# Solarladeregler.net
KiCad netlist of a schematic drawn in EAGLE
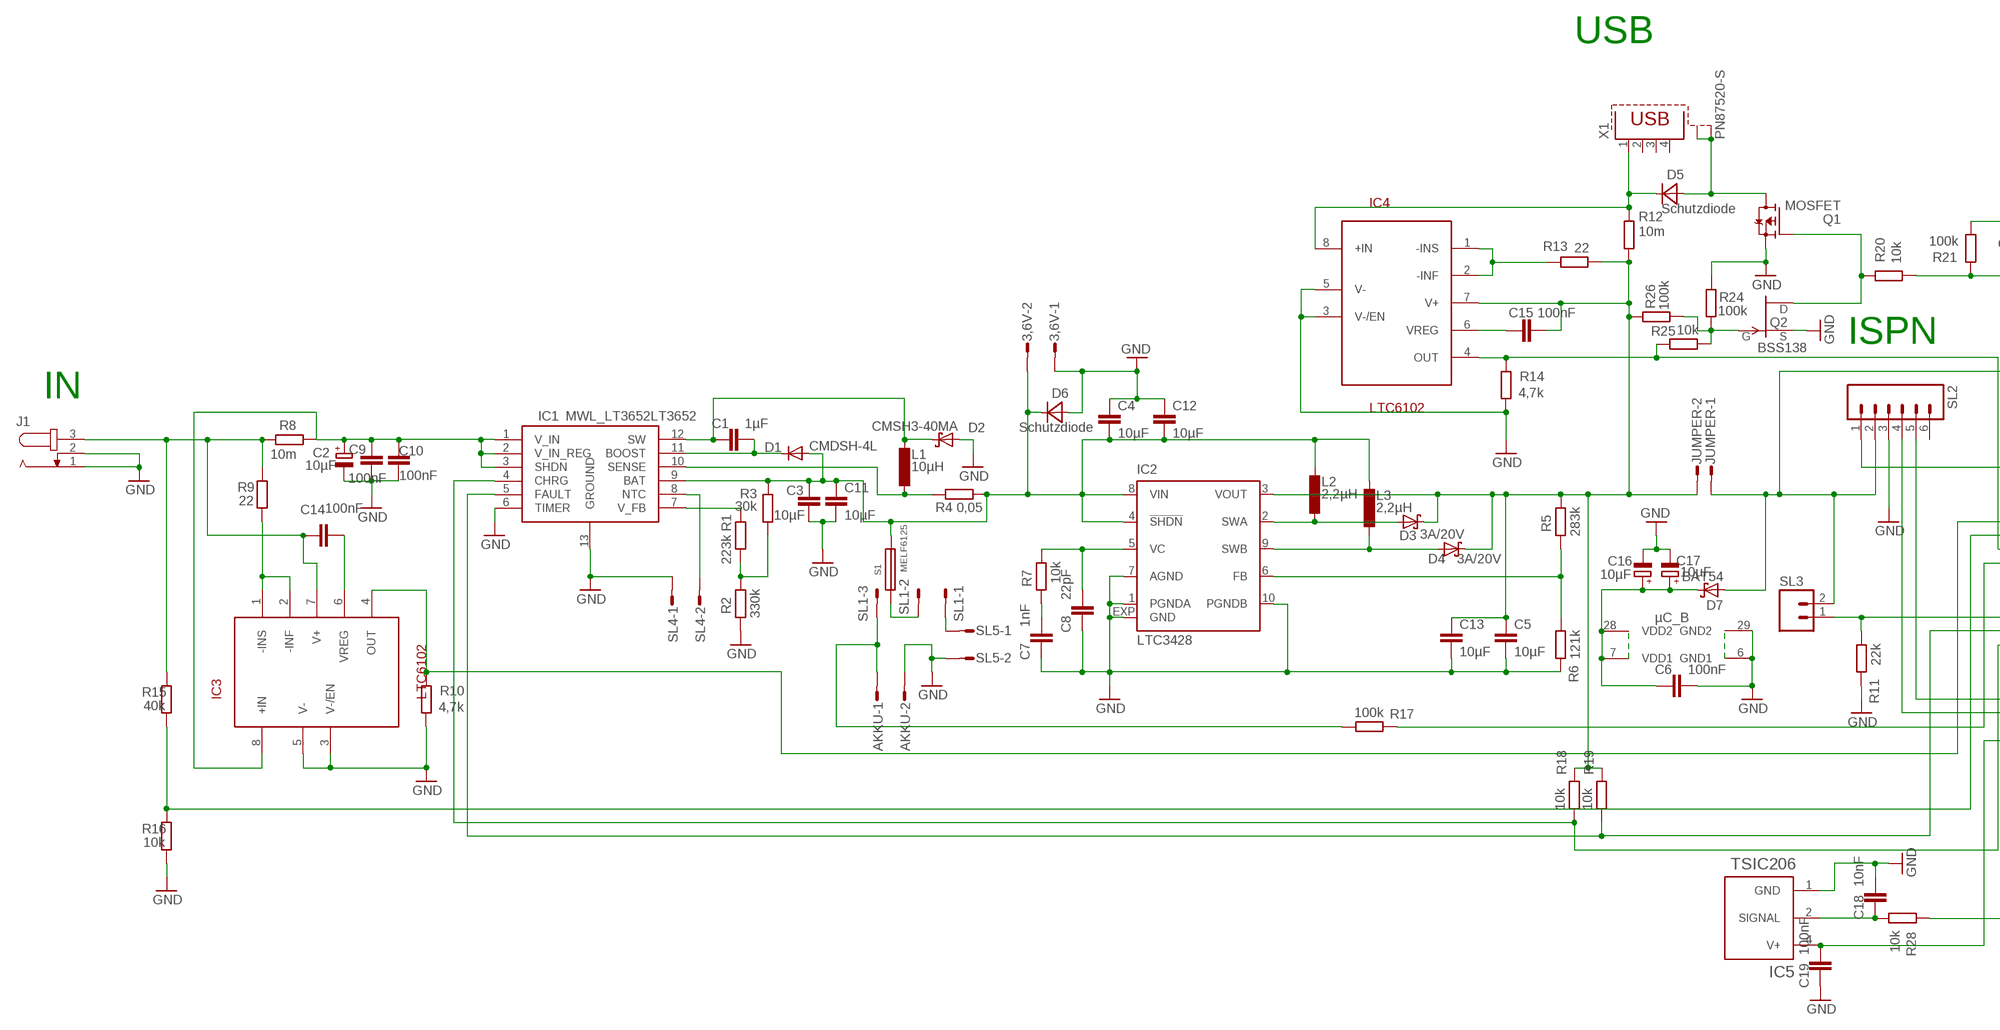
[diagram p0: schematic, sheet 1, part 1 of 2]
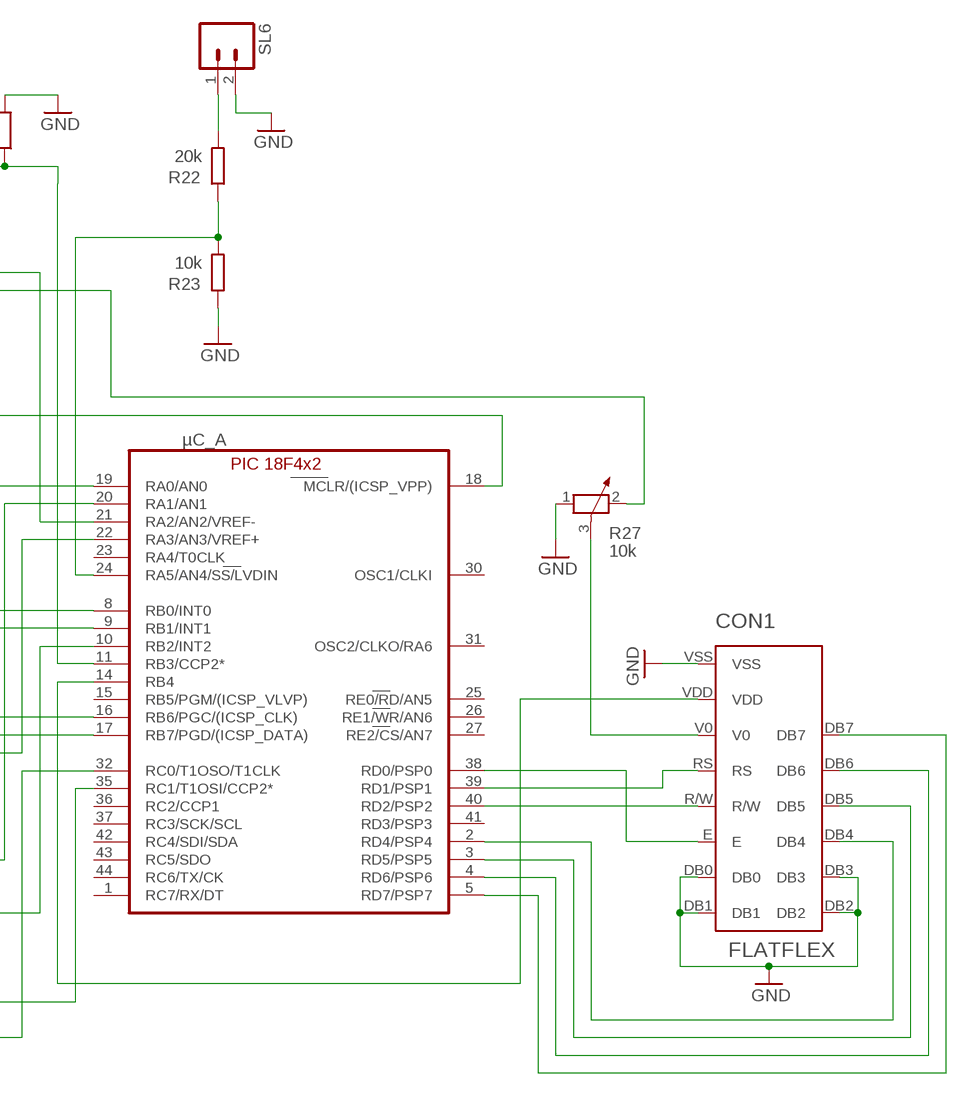
[diagram p1: schematic, sheet 1, part 2 of 2]

(export (version "E")
  (design (tool "Eeschema 10.0.6"))
  (components
    (comp (ref "3,6V")
      (value "M02S")
      (footprint "eagle-import:02P")
      (libsource (lib "eagle-import") (part "M02S"))
    )
    (comp (ref "AKKU")
      (value "M02S")
      (footprint "eagle-import:02P")
      (libsource (lib "eagle-import") (part "M02S"))
    )
    (comp (ref "C1")
      (value "1µF")
      (footprint "eagle-import:C0805")
      (libsource (lib "eagle-import") (part "C-EUC0805"))
    )
    (comp (ref "C2")
      (value "10µF")
      (footprint "eagle-import:153CLV-0505")
      (libsource (lib "eagle-import") (part "CPOL-EU153CLV-0505"))
    )
    (comp (ref "C3")
      (value "10µF")
      (footprint "eagle-import:C0805")
      (libsource (lib "eagle-import") (part "C-EUC0805"))
    )
    (comp (ref "C4")
      (value "10µF")
      (footprint "eagle-import:C0805")
      (libsource (lib "eagle-import") (part "C-EUC0805"))
    )
    (comp (ref "C5")
      (value "10µF")
      (footprint "eagle-import:C0805")
      (libsource (lib "eagle-import") (part "C-EUC0805"))
    )
    (comp (ref "C6")
      (value "100nF")
      (footprint "eagle-import:C0805")
      (libsource (lib "eagle-import") (part "C-EUC0805"))
    )
    (comp (ref "C7")
      (value "1nF")
      (footprint "eagle-import:C0805")
      (libsource (lib "eagle-import") (part "C-EUC0805"))
    )
    (comp (ref "C8")
      (value "22pF")
      (footprint "eagle-import:C0805")
      (libsource (lib "eagle-import") (part "C-EUC0805"))
    )
    (comp (ref "C9")
      (value "100nF")
      (footprint "eagle-import:C0805")
      (libsource (lib "eagle-import") (part "C-EUC0805"))
    )
    (comp (ref "C10")
      (value "100nF")
      (footprint "eagle-import:C0805")
      (libsource (lib "eagle-import") (part "C-EUC0805"))
    )
    (comp (ref "C11")
      (value "10µF")
      (footprint "eagle-import:C0805")
      (libsource (lib "eagle-import") (part "C-EUC0805"))
    )
    (comp (ref "C12")
      (value "10µF")
      (footprint "eagle-import:C0805")
      (libsource (lib "eagle-import") (part "C-EUC0805"))
    )
    (comp (ref "C13")
      (value "10µF")
      (footprint "eagle-import:C0805")
      (libsource (lib "eagle-import") (part "C-EUC0805"))
    )
    (comp (ref "C14")
      (value "100nF")
      (footprint "eagle-import:C0805")
      (libsource (lib "eagle-import") (part "C-EUC0805"))
    )
    (comp (ref "C15")
      (value "100nF")
      (footprint "eagle-import:C0805")
      (libsource (lib "eagle-import") (part "C-EUC0805"))
    )
    (comp (ref "C16")
      (value "10µF")
      (footprint "eagle-import:153CLV-0505")
      (libsource (lib "eagle-import") (part "CPOL-EU153CLV-0505"))
    )
    (comp (ref "C17")
      (value "10µF")
      (footprint "eagle-import:153CLV-0505")
      (libsource (lib "eagle-import") (part "CPOL-EU153CLV-0505"))
    )
    (comp (ref "C18")
      (value "10nF")
      (footprint "eagle-import:C0805")
      (libsource (lib "eagle-import") (part "C-EUC0805"))
    )
    (comp (ref "C19")
      (value "100nF")
      (footprint "eagle-import:C0805")
      (libsource (lib "eagle-import") (part "C-EUC0805"))
    )
    (comp (ref "CON1")
      (value "FLATFLEX")
      (footprint "eagle-import:FLATFLEX")
      (libsource (lib "eagle-import") (part "FLATFLEX"))
    )
    (comp (ref "D1")
      (value "CMDSH-4L")
      (footprint "eagle-import:SOD123")
      (libsource (lib "eagle-import") (part "MBR0520LT"))
    )
    (comp (ref "D2")
      (value "CMSH3-40MA")
      (footprint "eagle-import:SMB")
      (libsource (lib "eagle-import") (part "SCHOTTKY-DIODESMD"))
    )
    (comp (ref "D3")
      (value "3A/20V")
      (footprint "eagle-import:SMC")
      (libsource (lib "eagle-import") (part "MBRS30T32"))
    )
    (comp (ref "D4")
      (value "3A/20V")
      (footprint "eagle-import:SMC")
      (libsource (lib "eagle-import") (part "MBRS30T32"))
    )
    (comp (ref "D5")
      (value "Schutzdiode")
      (footprint "eagle-import:SMA")
      (libsource (lib "eagle-import") (part "MBRA340T3"))
    )
    (comp (ref "D6")
      (value "Schutzdiode")
      (footprint "eagle-import:SMA")
      (libsource (lib "eagle-import") (part "MBRA340T3"))
    )
    (comp (ref "D7")
      (value "BAT54")
      (footprint "eagle-import:SOT23")
      (libsource (lib "eagle-import") (part "BAT54"))
    )
    (comp (ref "IC1")
      (value "MWL_LT3652LT3652")
      (footprint "eagle-import:DFN12DD3X3")
      (libsource (lib "eagle-import") (part "MWL_LT3652LT3652"))
    )
    (comp (ref "IC2")
      (value "LTC3428")
      (footprint "eagle-import:DFN10-3X3")
      (libsource (lib "eagle-import") (part "LTC3428"))
    )
    (comp (ref "IC3")
      (value "LTC6102")
      (footprint "eagle-import:MSOP8")
      (libsource (lib "eagle-import") (part "LTC6102"))
    )
    (comp (ref "IC4")
      (value "LTC6102")
      (footprint "eagle-import:MSOP8")
      (libsource (lib "eagle-import") (part "LTC6102"))
    )
    (comp (ref "IC5")
      (value "TSIC206")
      (footprint "eagle-import:SO08")
      (libsource (lib "eagle-import") (part "TSIC206"))
    )
    (comp (ref "J1")
      (value "JACK-PLUG0")
      (footprint "eagle-import:SPC4077")
      (libsource (lib "eagle-import") (part "JACK-PLUG0"))
    )
    (comp (ref "JUMPER")
      (value "M02S")
      (footprint "eagle-import:02P")
      (libsource (lib "eagle-import") (part "M02S"))
    )
    (comp (ref "L1")
      (value "10µH")
      (footprint "eagle-import:POWER-CHOKE_WE-TPC")
      (libsource (lib "eagle-import") (part "L-EUWE-TPC"))
    )
    (comp (ref "L2")
      (value "2,2µH")
      (footprint "eagle-import:POWER-CHOKE_WE-TPC")
      (libsource (lib "eagle-import") (part "L-EUWE-TPC"))
    )
    (comp (ref "L3")
      (value "2,2µH")
      (footprint "eagle-import:POWER-CHOKE_WE-TPC")
      (libsource (lib "eagle-import") (part "L-EUWE-TPC"))
    )
    (comp (ref "Q1")
      (value "MOSFET")
      (footprint "eagle-import:TO252")
      (libsource (lib "eagle-import") (part "FDD4141TO252"))
    )
    (comp (ref "Q2")
      (value "BSS138")
      (footprint "eagle-import:SOT23")
      (libsource (lib "eagle-import") (part "?548SST4"))
    )
    (comp (ref "R1")
      (value "223k")
      (footprint "eagle-import:R0805")
      (libsource (lib "eagle-import") (part "R-EU_R0805"))
    )
    (comp (ref "R2")
      (value "330k")
      (footprint "eagle-import:R0805")
      (libsource (lib "eagle-import") (part "R-EU_R0805"))
    )
    (comp (ref "R3")
      (value "30k")
      (footprint "eagle-import:R0805")
      (libsource (lib "eagle-import") (part "R-EU_R0805"))
    )
    (comp (ref "R4")
      (value "0,05")
      (footprint "eagle-import:R0805")
      (libsource (lib "eagle-import") (part "R-EU_R0805"))
    )
    (comp (ref "R5")
      (value "283k")
      (footprint "eagle-import:R0805")
      (libsource (lib "eagle-import") (part "R-EU_R0805"))
    )
    (comp (ref "R6")
      (value "121k")
      (footprint "eagle-import:R0805")
      (libsource (lib "eagle-import") (part "R-EU_R0805"))
    )
    (comp (ref "R7")
      (value "10k")
      (footprint "eagle-import:R0805")
      (libsource (lib "eagle-import") (part "R-EU_R0805"))
    )
    (comp (ref "R8")
      (value "10m")
      (footprint "eagle-import:R2512")
      (libsource (lib "eagle-import") (part "R-EU_R2512"))
    )
    (comp (ref "R9")
      (value "22")
      (footprint "eagle-import:R0805")
      (libsource (lib "eagle-import") (part "R-EU_R0805"))
    )
    (comp (ref "R10")
      (value "4,7k")
      (footprint "eagle-import:R0805")
      (libsource (lib "eagle-import") (part "R-EU_R0805"))
    )
    (comp (ref "R11")
      (value "22k")
      (footprint "eagle-import:R0805")
      (libsource (lib "eagle-import") (part "R-EU_R0805"))
    )
    (comp (ref "R12")
      (value "10m")
      (footprint "eagle-import:R2512")
      (libsource (lib "eagle-import") (part "R-EU_R2512"))
    )
    (comp (ref "R13")
      (value "22")
      (footprint "eagle-import:R0805")
      (libsource (lib "eagle-import") (part "R-EU_R0805"))
    )
    (comp (ref "R14")
      (value "4,7k")
      (footprint "eagle-import:R0805")
      (libsource (lib "eagle-import") (part "R-EU_R0805"))
    )
    (comp (ref "R15")
      (value "40k")
      (footprint "eagle-import:R0805")
      (libsource (lib "eagle-import") (part "R-EU_R0805"))
    )
    (comp (ref "R16")
      (value "10k")
      (footprint "eagle-import:R0805")
      (libsource (lib "eagle-import") (part "R-EU_R0805"))
    )
    (comp (ref "R17")
      (value "100k")
      (footprint "eagle-import:R0805")
      (libsource (lib "eagle-import") (part "R-EU_R0805"))
    )
    (comp (ref "R18")
      (value "10k")
      (footprint "eagle-import:R0805")
      (libsource (lib "eagle-import") (part "R-EU_R0805"))
    )
    (comp (ref "R19")
      (value "10k")
      (footprint "eagle-import:R0805")
      (libsource (lib "eagle-import") (part "R-EU_R0805"))
    )
    (comp (ref "R20")
      (value "10k")
      (footprint "eagle-import:R0805")
      (libsource (lib "eagle-import") (part "R-EU_R0805"))
    )
    (comp (ref "R21")
      (value "100k")
      (footprint "eagle-import:R0805")
      (libsource (lib "eagle-import") (part "R-EU_R0805"))
    )
    (comp (ref "R22")
      (value "20k")
      (footprint "eagle-import:R0805")
      (libsource (lib "eagle-import") (part "R-EU_R0805"))
    )
    (comp (ref "R23")
      (value "10k")
      (footprint "eagle-import:R0805")
      (libsource (lib "eagle-import") (part "R-EU_R0805"))
    )
    (comp (ref "R24")
      (value "100k")
      (footprint "eagle-import:R0805")
      (libsource (lib "eagle-import") (part "R-EU_R0805"))
    )
    (comp (ref "R25")
      (value "10k")
      (footprint "eagle-import:R0805")
      (libsource (lib "eagle-import") (part "R-EU_R0805"))
    )
    (comp (ref "R26")
      (value "100k")
      (footprint "eagle-import:R0805")
      (libsource (lib "eagle-import") (part "R-EU_R0805"))
    )
    (comp (ref "R27")
      (value "10k")
      (footprint "eagle-import:PT-10")
      (libsource (lib "eagle-import") (part "POTENTIOMETER_PT-10"))
    )
    (comp (ref "R28")
      (value "10k")
      (footprint "eagle-import:R0805")
      (libsource (lib "eagle-import") (part "R-EU_R0805"))
    )
    (comp (ref "S1")
      (value "MELF6125")
      (footprint "eagle-import:MELF6125")
      (libsource (lib "eagle-import") (part "MELF6125"))
    )
    (comp (ref "SL1")
      (value "M03S")
      (footprint "eagle-import:03P")
      (libsource (lib "eagle-import") (part "M03S"))
    )
    (comp (ref "SL2")
      (value "M06")
      (footprint "eagle-import:06P")
      (libsource (lib "eagle-import") (part "M06"))
    )
    (comp (ref "SL3")
      (value "M02")
      (footprint "eagle-import:02P")
      (libsource (lib "eagle-import") (part "M02"))
    )
    (comp (ref "SL4")
      (value "M02S")
      (footprint "eagle-import:02P")
      (libsource (lib "eagle-import") (part "M02S"))
    )
    (comp (ref "SL5")
      (value "M02S")
      (footprint "eagle-import:02P")
      (libsource (lib "eagle-import") (part "M02S"))
    )
    (comp (ref "SL6")
      (value "M02")
      (footprint "eagle-import:02P")
      (libsource (lib "eagle-import") (part "M02"))
    )
    (comp (ref "X1")
      (value "PN87520-S")
      (footprint "eagle-import:PN87520-S")
      (libsource (lib "eagle-import") (part "PN87520-S"))
    )
    (comp (ref "µC")
      (value "PIC18F4X2TQFP44")
      (footprint "eagle-import:TQFP44")
      (libsource (lib "eagle-import") (part "PIC18F4X2TQFP44"))
    )
  )
  (nets
    (net (code "1") (name "/OSC1{slash}CLKI") (class "Default")
      (node (ref "µC") (pin "30") (pinfunction "OSC1/CLKI_30") (pintype "power_in"))
    )
    (net (code "2") (name "/OSC2{slash}CLKO{slash}RA6") (class "Default")
      (node (ref "µC") (pin "31") (pinfunction "OSC2/CLKO/RA6_31") (pintype "power_in"))
    )
    (net (code "3") (name "GND") (class "Default")
      (node (ref "3,6V") (pin "1") (pinfunction "S_1") (pintype "passive"))
      (node (ref "AKKU") (pin "2") (pinfunction "S_2") (pintype "passive"))
      (node (ref "C10") (pin "2") (pinfunction "2_2") (pintype "passive"))
      (node (ref "C11") (pin "2") (pinfunction "2_2") (pintype "passive"))
      (node (ref "C12") (pin "1") (pinfunction "1_1") (pintype "passive"))
      (node (ref "C13") (pin "2") (pinfunction "2_2") (pintype "passive"))
      (node (ref "C16") (pin "-") (pinfunction "-_-") (pintype "passive"))
      (node (ref "C17") (pin "-") (pinfunction "-_-") (pintype "passive"))
      (node (ref "C18") (pin "1") (pinfunction "1_1") (pintype "passive"))
      (node (ref "C19") (pin "2") (pinfunction "2_2") (pintype "passive"))
      (node (ref "C2") (pin "-") (pinfunction "-_-") (pintype "passive"))
      (node (ref "C3") (pin "2") (pinfunction "2_2") (pintype "passive"))
      (node (ref "C4") (pin "1") (pinfunction "1_1") (pintype "passive"))
      (node (ref "C5") (pin "2") (pinfunction "2_2") (pintype "passive"))
      (node (ref "C6") (pin "1") (pinfunction "1_1") (pintype "passive"))
      (node (ref "C7") (pin "2") (pinfunction "2_2") (pintype "passive"))
      (node (ref "C8") (pin "2") (pinfunction "2_2") (pintype "passive"))
      (node (ref "C9") (pin "2") (pinfunction "2_2") (pintype "passive"))
      (node (ref "CON1") (pin "DB0") (pinfunction "DB0_DB0") (pintype "bidirectional"))
      (node (ref "CON1") (pin "DB1") (pinfunction "DB1_DB1") (pintype "bidirectional"))
      (node (ref "CON1") (pin "DB2") (pinfunction "DB2_DB2") (pintype "bidirectional"))
      (node (ref "CON1") (pin "DB3") (pinfunction "DB3_DB3") (pintype "bidirectional"))
      (node (ref "CON1") (pin "VSS") (pinfunction "VSS_VSS") (pintype "bidirectional"))
      (node (ref "D2") (pin "A") (pinfunction "A_A") (pintype "passive"))
      (node (ref "D6") (pin "A") (pinfunction "A_A") (pintype "passive"))
      (node (ref "IC1") (pin "13") (pinfunction "GROUND_13") (pintype "bidirectional"))
      (node (ref "IC1") (pin "6") (pinfunction "TIMER_6") (pintype "bidirectional"))
      (node (ref "IC2") (pin "1") (pinfunction "PGNDA_1") (pintype "passive"))
      (node (ref "IC2") (pin "10") (pinfunction "PGNDB_10") (pintype "passive"))
      (node (ref "IC2") (pin "7") (pinfunction "AGND_7") (pintype "passive"))
      (node (ref "IC2") (pin "EXP") (pinfunction "GND_EXP") (pintype "power_in"))
      (node (ref "IC3") (pin "3") (pinfunction "V-/EN_3") (pintype "bidirectional"))
      (node (ref "IC3") (pin "5") (pinfunction "V-_5") (pintype "bidirectional"))
      (node (ref "IC4") (pin "3") (pinfunction "V-/EN_3") (pintype "bidirectional"))
      (node (ref "IC4") (pin "5") (pinfunction "V-_5") (pintype "bidirectional"))
      (node (ref "IC5") (pin "1") (pinfunction "GND_1") (pintype "bidirectional"))
      (node (ref "J1") (pin "1") (pinfunction "1_1") (pintype "passive"))
      (node (ref "J1") (pin "2") (pinfunction "2_2") (pintype "passive"))
      (node (ref "Q1") (pin "2") (pinfunction "S_2") (pintype "passive"))
      (node (ref "Q2") (pin "2") (pinfunction "S_2") (pintype "passive"))
      (node (ref "R10") (pin "2") (pinfunction "2_2") (pintype "passive"))
      (node (ref "R11") (pin "2") (pinfunction "2_2") (pintype "passive"))
      (node (ref "R14") (pin "2") (pinfunction "2_2") (pintype "passive"))
      (node (ref "R16") (pin "2") (pinfunction "2_2") (pintype "passive"))
      (node (ref "R2") (pin "2") (pinfunction "2_2") (pintype "passive"))
      (node (ref "R21") (pin "2") (pinfunction "2_2") (pintype "passive"))
      (node (ref "R23") (pin "1") (pinfunction "1_1") (pintype "passive"))
      (node (ref "R24") (pin "1") (pinfunction "1_1") (pintype "passive"))
      (node (ref "R27") (pin "1") (pinfunction "1_1") (pintype "passive"))
      (node (ref "R6") (pin "2") (pinfunction "2_2") (pintype "passive"))
      (node (ref "SL2") (pin "3") (pinfunction "3_3") (pintype "passive"))
      (node (ref "SL4") (pin "1") (pinfunction "S_1") (pintype "passive"))
      (node (ref "SL5") (pin "2") (pinfunction "S_2") (pintype "passive"))
      (node (ref "SL6") (pin "2") (pinfunction "2_2") (pintype "passive"))
      (node (ref "µC") (pin "29") (pinfunction "GND2_29") (pintype "power_in"))
      (node (ref "µC") (pin "6") (pinfunction "GND1_6") (pintype "power_in"))
    )
    (net (code "4") (name "Net-(3,6VB-S)") (class "Default")
      (node (ref "3,6V") (pin "2") (pinfunction "S_2") (pintype "passive"))
      (node (ref "C11") (pin "1") (pinfunction "1_1") (pintype "passive"))
      (node (ref "C12") (pin "2") (pinfunction "2_2") (pintype "passive"))
      (node (ref "C3") (pin "1") (pinfunction "1_1") (pintype "passive"))
      (node (ref "C4") (pin "2") (pinfunction "2_2") (pintype "passive"))
      (node (ref "D1") (pin "A") (pinfunction "A_A") (pintype "passive"))
      (node (ref "D6") (pin "C") (pinfunction "C_C") (pintype "passive"))
      (node (ref "IC1") (pin "9") (pinfunction "BAT_9") (pintype "output"))
      (node (ref "IC2") (pin "4") (pinfunction "~{SHDN}_4") (pintype "open_collector"))
      (node (ref "IC2") (pin "8") (pinfunction "VIN_8") (pintype "power_in"))
      (node (ref "L2") (pin "2") (pinfunction "2_2") (pintype "passive"))
      (node (ref "L3") (pin "2") (pinfunction "2_2") (pintype "passive"))
      (node (ref "R3") (pin "2") (pinfunction "2_2") (pintype "passive"))
      (node (ref "R4") (pin "1") (pinfunction "1_1") (pintype "passive"))
      (node (ref "S1") (pin "P$4") (pinfunction "P$2_P$4") (pintype "bidirectional"))
    )
    (net (code "5") (name "Net-(AKKUA-S)") (class "Default")
      (node (ref "AKKU") (pin "1") (pinfunction "S_1") (pintype "passive"))
      (node (ref "R17") (pin "1") (pinfunction "1_1") (pintype "passive"))
      (node (ref "SL1") (pin "3") (pinfunction "S_3") (pintype "passive"))
    )
    (net (code "6") (name "Net-(C7-Pad1)") (class "Default")
      (node (ref "C7") (pin "1") (pinfunction "1_1") (pintype "passive"))
      (node (ref "R7") (pin "2") (pinfunction "2_2") (pintype "passive"))
    )
    (net (code "7") (name "Net-(CON1-PadV0)") (class "Default")
      (node (ref "CON1") (pin "V0") (pinfunction "V0_V0") (pintype "bidirectional"))
      (node (ref "R27") (pin "3") (pinfunction "3_3") (pintype "passive"))
    )
    (net (code "8") (name "Net-(D7-A)") (class "Default")
      (node (ref "D7") (pin "1") (pinfunction "A_1") (pintype "passive"))
      (node (ref "JUMPER") (pin "1") (pinfunction "S_1") (pintype "passive"))
      (node (ref "R27") (pin "2") (pinfunction "2_2") (pintype "passive"))
      (node (ref "SL2") (pin "2") (pinfunction "2_2") (pintype "passive"))
      (node (ref "SL3") (pin "2") (pinfunction "2_2") (pintype "passive"))
    )
    (net (code "9") (name "Net-(D7-C)") (class "Default")
      (node (ref "C16") (pin "+") (pinfunction "+_+") (pintype "passive"))
      (node (ref "C17") (pin "+") (pinfunction "+_+") (pintype "passive"))
      (node (ref "C6") (pin "2") (pinfunction "2_2") (pintype "passive"))
      (node (ref "D7") (pin "3") (pinfunction "C_3") (pintype "passive"))
      (node (ref "µC") (pin "28") (pinfunction "VDD2_28") (pintype "power_in"))
      (node (ref "µC") (pin "7") (pinfunction "VDD1_7") (pintype "power_in"))
    )
    (net (code "10") (name "Net-(IC1-BOOST)") (class "Default")
      (node (ref "C1") (pin "1") (pinfunction "1_1") (pintype "passive"))
      (node (ref "D1") (pin "C") (pinfunction "C_C") (pintype "passive"))
      (node (ref "IC1") (pin "11") (pinfunction "BOOST_11") (pintype "bidirectional"))
    )
    (net (code "11") (name "Net-(IC1-CHRG)") (class "Default")
      (node (ref "IC1") (pin "4") (pinfunction "CHRG_4") (pintype "output"))
      (node (ref "R18") (pin "1") (pinfunction "1_1") (pintype "passive"))
      (node (ref "µC") (pin "10") (pinfunction "RB2/INT2_10") (pintype "bidirectional"))
    )
    (net (code "12") (name "Net-(IC1-FAULT)") (class "Default")
      (node (ref "IC1") (pin "5") (pinfunction "FAULT_5") (pintype "output"))
      (node (ref "R19") (pin "1") (pinfunction "1_1") (pintype "passive"))
      (node (ref "µC") (pin "9") (pinfunction "RB1/INT1_9") (pintype "bidirectional"))
    )
    (net (code "13") (name "Net-(IC1-NTC)") (class "Default")
      (node (ref "IC1") (pin "8") (pinfunction "NTC_8") (pintype "input"))
      (node (ref "SL4") (pin "2") (pinfunction "S_2") (pintype "passive"))
    )
    (net (code "14") (name "Net-(IC1-SENSE)") (class "Default")
      (node (ref "IC1") (pin "10") (pinfunction "SENSE_10") (pintype "bidirectional"))
      (node (ref "L1") (pin "1") (pinfunction "1_1") (pintype "passive"))
      (node (ref "R4") (pin "2") (pinfunction "2_2") (pintype "passive"))
    )
    (net (code "15") (name "Net-(IC1-SHDN)") (class "Default")
      (node (ref "C10") (pin "1") (pinfunction "1_1") (pintype "passive"))
      (node (ref "C2") (pin "+") (pinfunction "+_+") (pintype "passive"))
      (node (ref "C9") (pin "1") (pinfunction "1_1") (pintype "passive"))
      (node (ref "IC1") (pin "1") (pinfunction "V_IN_1") (pintype "input"))
      (node (ref "IC1") (pin "2") (pinfunction "V_IN_REG_2") (pintype "input"))
      (node (ref "IC1") (pin "3") (pinfunction "SHDN_3") (pintype "input"))
      (node (ref "IC3") (pin "8") (pinfunction "+IN_8") (pintype "bidirectional"))
      (node (ref "R8") (pin "1") (pinfunction "1_1") (pintype "passive"))
    )
    (net (code "16") (name "Net-(IC1-SW)") (class "Default")
      (node (ref "C1") (pin "2") (pinfunction "2_2") (pintype "passive"))
      (node (ref "D2") (pin "C") (pinfunction "C_C") (pintype "passive"))
      (node (ref "IC1") (pin "12") (pinfunction "SW_12") (pintype "output"))
      (node (ref "L1") (pin "2") (pinfunction "2_2") (pintype "passive"))
    )
    (net (code "17") (name "Net-(IC1-V_FB)") (class "Default")
      (node (ref "IC1") (pin "7") (pinfunction "V_FB_7") (pintype "bidirectional"))
      (node (ref "R1") (pin "1") (pinfunction "1_1") (pintype "passive"))
    )
    (net (code "18") (name "Net-(IC2-FB)") (class "Default")
      (node (ref "IC2") (pin "6") (pinfunction "FB_6") (pintype "input"))
      (node (ref "R5") (pin "2") (pinfunction "2_2") (pintype "passive"))
      (node (ref "R6") (pin "1") (pinfunction "1_1") (pintype "passive"))
    )
    (net (code "19") (name "Net-(IC2-SWA)") (class "Default")
      (node (ref "D3") (pin "A") (pinfunction "A_A") (pintype "passive"))
      (node (ref "IC2") (pin "2") (pinfunction "SWA_2") (pintype "open_collector"))
      (node (ref "L2") (pin "1") (pinfunction "1_1") (pintype "passive"))
    )
    (net (code "20") (name "Net-(IC2-SWB)") (class "Default")
      (node (ref "D4") (pin "A") (pinfunction "A_A") (pintype "passive"))
      (node (ref "IC2") (pin "9") (pinfunction "SWB_9") (pintype "passive"))
      (node (ref "L3") (pin "1") (pinfunction "1_1") (pintype "passive"))
    )
    (net (code "21") (name "Net-(IC2-VC)") (class "Default")
      (node (ref "C8") (pin "1") (pinfunction "1_1") (pintype "passive"))
      (node (ref "IC2") (pin "5") (pinfunction "VC_5") (pintype "input"))
      (node (ref "R7") (pin "1") (pinfunction "1_1") (pintype "passive"))
    )
    (net (code "22") (name "Net-(IC2-VOUT)") (class "Default")
      (node (ref "C13") (pin "1") (pinfunction "1_1") (pintype "passive"))
      (node (ref "C15") (pin "2") (pinfunction "2_2") (pintype "passive"))
      (node (ref "C5") (pin "1") (pinfunction "1_1") (pintype "passive"))
      (node (ref "D3") (pin "C") (pinfunction "C_C") (pintype "passive"))
      (node (ref "D4") (pin "C") (pinfunction "C_C") (pintype "passive"))
      (node (ref "IC2") (pin "3") (pinfunction "VOUT_3") (pintype "input"))
      (node (ref "IC4") (pin "7") (pinfunction "V+_7") (pintype "bidirectional"))
      (node (ref "JUMPER") (pin "2") (pinfunction "S_2") (pintype "passive"))
      (node (ref "R12") (pin "2") (pinfunction "2_2") (pintype "passive"))
      (node (ref "R13") (pin "2") (pinfunction "2_2") (pintype "passive"))
      (node (ref "R18") (pin "2") (pinfunction "2_2") (pintype "passive"))
      (node (ref "R19") (pin "2") (pinfunction "2_2") (pintype "passive"))
      (node (ref "R26") (pin "1") (pinfunction "1_1") (pintype "passive"))
      (node (ref "R5") (pin "1") (pinfunction "1_1") (pintype "passive"))
    )
    (net (code "23") (name "Net-(IC3--INF)") (class "Default")
      (node (ref "IC3") (pin "1") (pinfunction "-INS_1") (pintype "bidirectional"))
      (node (ref "IC3") (pin "2") (pinfunction "-INF_2") (pintype "bidirectional"))
      (node (ref "R9") (pin "2") (pinfunction "2_2") (pintype "passive"))
    )
    (net (code "24") (name "Net-(IC3-OUT)") (class "Default")
      (node (ref "IC3") (pin "4") (pinfunction "OUT_4") (pintype "bidirectional"))
      (node (ref "R10") (pin "1") (pinfunction "1_1") (pintype "passive"))
      (node (ref "µC") (pin "19") (pinfunction "RA0/AN0_19") (pintype "bidirectional"))
    )
    (net (code "25") (name "Net-(IC3-V+)") (class "Default")
      (node (ref "C14") (pin "1") (pinfunction "1_1") (pintype "passive"))
      (node (ref "IC3") (pin "7") (pinfunction "V+_7") (pintype "bidirectional"))
      (node (ref "J1") (pin "3") (pinfunction "3_3") (pintype "passive"))
      (node (ref "R15") (pin "1") (pinfunction "1_1") (pintype "passive"))
      (node (ref "R8") (pin "2") (pinfunction "2_2") (pintype "passive"))
      (node (ref "R9") (pin "1") (pinfunction "1_1") (pintype "passive"))
    )
    (net (code "26") (name "Net-(IC3-VREG)") (class "Default")
      (node (ref "C14") (pin "2") (pinfunction "2_2") (pintype "passive"))
      (node (ref "IC3") (pin "6") (pinfunction "VREG_6") (pintype "bidirectional"))
    )
    (net (code "27") (name "Net-(IC4-+IN)") (class "Default")
      (node (ref "D5") (pin "C") (pinfunction "C_C") (pintype "passive"))
      (node (ref "IC4") (pin "8") (pinfunction "+IN_8") (pintype "bidirectional"))
      (node (ref "R12") (pin "1") (pinfunction "1_1") (pintype "passive"))
      (node (ref "X1") (pin "1") (pinfunction "1_1") (pintype "passive"))
    )
    (net (code "28") (name "Net-(IC4--INF)") (class "Default")
      (node (ref "IC4") (pin "1") (pinfunction "-INS_1") (pintype "bidirectional"))
      (node (ref "IC4") (pin "2") (pinfunction "-INF_2") (pintype "bidirectional"))
      (node (ref "R13") (pin "1") (pinfunction "1_1") (pintype "passive"))
    )
    (net (code "29") (name "Net-(IC4-OUT)") (class "Default")
      (node (ref "IC4") (pin "4") (pinfunction "OUT_4") (pintype "bidirectional"))
      (node (ref "R14") (pin "1") (pinfunction "1_1") (pintype "passive"))
      (node (ref "R25") (pin "1") (pinfunction "1_1") (pintype "passive"))
      (node (ref "µC") (pin "21") (pinfunction "RA2/AN2/VREF-_21") (pintype "bidirectional"))
    )
    (net (code "30") (name "Net-(IC4-VREG)") (class "Default")
      (node (ref "C15") (pin "1") (pinfunction "1_1") (pintype "passive"))
      (node (ref "IC4") (pin "6") (pinfunction "VREG_6") (pintype "bidirectional"))
    )
    (net (code "31") (name "Net-(IC5-SIGNAL)") (class "Default")
      (node (ref "C18") (pin "2") (pinfunction "2_2") (pintype "passive"))
      (node (ref "IC5") (pin "2") (pinfunction "SIGNAL_2") (pintype "bidirectional"))
      (node (ref "R28") (pin "2") (pinfunction "2_2") (pintype "passive"))
    )
    (net (code "32") (name "Net-(IC5-V+)") (class "Default")
      (node (ref "C19") (pin "1") (pinfunction "1_1") (pintype "passive"))
      (node (ref "IC5") (pin "4") (pinfunction "V+_4") (pintype "bidirectional"))
      (node (ref "µC") (pin "32") (pinfunction "RC0/T1OSO/T1CLK_32") (pintype "bidirectional"))
    )
    (net (code "33") (name "Net-(Q1-D)") (class "Default")
      (node (ref "D5") (pin "A") (pinfunction "A_A") (pintype "passive"))
      (node (ref "Q1") (pin "3") (pinfunction "D_3") (pintype "passive"))
      (node (ref "X1") (pin "S1") (pinfunction "S1_S1") (pintype "passive"))
      (node (ref "X1") (pin "S2") (pinfunction "S2_S2") (pintype "passive"))
    )
    (net (code "34") (name "Net-(Q1-G)") (class "Default")
      (node (ref "Q1") (pin "1") (pinfunction "G_1") (pintype "passive"))
      (node (ref "Q2") (pin "1") (pinfunction "D_1") (pintype "passive"))
      (node (ref "R20") (pin "1") (pinfunction "1_1") (pintype "passive"))
    )
    (net (code "35") (name "Net-(Q2-G)") (class "Default")
      (node (ref "Q2") (pin "3") (pinfunction "G_3") (pintype "passive"))
      (node (ref "R24") (pin "2") (pinfunction "2_2") (pintype "passive"))
      (node (ref "R25") (pin "2") (pinfunction "2_2") (pintype "passive"))
      (node (ref "R26") (pin "2") (pinfunction "2_2") (pintype "passive"))
    )
    (net (code "36") (name "Net-(R1-Pad2)") (class "Default")
      (node (ref "R1") (pin "2") (pinfunction "2_2") (pintype "passive"))
      (node (ref "R2") (pin "1") (pinfunction "1_1") (pintype "passive"))
      (node (ref "R3") (pin "1") (pinfunction "1_1") (pintype "passive"))
    )
    (net (code "37") (name "Net-(R22-Pad2)") (class "Default")
      (node (ref "R22") (pin "2") (pinfunction "2_2") (pintype "passive"))
      (node (ref "SL6") (pin "1") (pinfunction "1_1") (pintype "passive"))
    )
    (net (code "38") (name "Net-(S1-P$1)") (class "Default")
      (node (ref "S1") (pin "P$3") (pinfunction "P$1_P$3") (pintype "bidirectional"))
      (node (ref "SL1") (pin "2") (pinfunction "S_2") (pintype "passive"))
    )
    (net (code "39") (name "Net-(SL1A-S)") (class "Default")
      (node (ref "SL1") (pin "1") (pinfunction "S_1") (pintype "passive"))
      (node (ref "SL5") (pin "1") (pinfunction "S_1") (pintype "passive"))
    )
    (net (code "40") (name "Net-(µCA-MCLR{slash}(ICSP_VPP))") (class "Default")
      (node (ref "SL2") (pin "1") (pinfunction "1_1") (pintype "passive"))
      (node (ref "µC") (pin "18") (pinfunction "MCLR/(ICSP_VPP)_18") (pintype "power_in"))
    )
    (net (code "41") (name "Net-(µCA-RA1{slash}AN1)") (class "Default")
      (node (ref "R15") (pin "2") (pinfunction "2_2") (pintype "passive"))
      (node (ref "R16") (pin "1") (pinfunction "1_1") (pintype "passive"))
      (node (ref "µC") (pin "20") (pinfunction "RA1/AN1_20") (pintype "bidirectional"))
    )
    (net (code "42") (name "Net-(µCA-RA3{slash}AN3{slash}VREF+)") (class "Default")
      (node (ref "R17") (pin "2") (pinfunction "2_2") (pintype "passive"))
      (node (ref "µC") (pin "22") (pinfunction "RA3/AN3/VREF+_22") (pintype "bidirectional"))
    )
    (net (code "43") (name "Net-(µCA-RA5{slash}AN4{slash}SS{slash}LVDIN)") (class "Default")
      (node (ref "R22") (pin "1") (pinfunction "1_1") (pintype "passive"))
      (node (ref "R23") (pin "2") (pinfunction "2_2") (pintype "passive"))
      (node (ref "µC") (pin "24") (pinfunction "RA5/AN4/SS/LVDIN_24") (pintype "bidirectional"))
    )
    (net (code "44") (name "Net-(µCA-RB0{slash}INT0)") (class "Default")
      (node (ref "R11") (pin "1") (pinfunction "1_1") (pintype "passive"))
      (node (ref "SL3") (pin "1") (pinfunction "1_1") (pintype "passive"))
      (node (ref "µC") (pin "8") (pinfunction "RB0/INT0_8") (pintype "bidirectional"))
    )
    (net (code "45") (name "Net-(µCA-RB3{slash}CCP2*)") (class "Default")
      (node (ref "R20") (pin "2") (pinfunction "2_2") (pintype "passive"))
      (node (ref "R21") (pin "1") (pinfunction "1_1") (pintype "passive"))
      (node (ref "µC") (pin "11") (pinfunction "RB3/CCP2*_11") (pintype "bidirectional"))
    )
    (net (code "46") (name "Net-(µCA-RB4)") (class "Default")
      (node (ref "CON1") (pin "VDD") (pinfunction "VDD_VDD") (pintype "bidirectional"))
      (node (ref "µC") (pin "14") (pinfunction "RB4_14") (pintype "bidirectional"))
    )
    (net (code "47") (name "Net-(µCA-RB6{slash}PGC{slash}(ICSP_CLK))") (class "Default")
      (node (ref "SL2") (pin "5") (pinfunction "5_5") (pintype "passive"))
      (node (ref "µC") (pin "16") (pinfunction "RB6/PGC/(ICSP_CLK)_16") (pintype "bidirectional"))
    )
    (net (code "48") (name "Net-(µCA-RB7{slash}PGD{slash}(ICSP_DATA))") (class "Default")
      (node (ref "SL2") (pin "4") (pinfunction "4_4") (pintype "passive"))
      (node (ref "µC") (pin "17") (pinfunction "RB7/PGD/(ICSP_DATA)_17") (pintype "bidirectional"))
    )
    (net (code "49") (name "Net-(µCA-RC1{slash}T1OSI{slash}CCP2*)") (class "Default")
      (node (ref "R28") (pin "1") (pinfunction "1_1") (pintype "passive"))
      (node (ref "µC") (pin "35") (pinfunction "RC1/T1OSI/CCP2*_35") (pintype "bidirectional"))
    )
    (net (code "50") (name "Net-(µCA-RD0{slash}PSP0)") (class "Default")
      (node (ref "CON1") (pin "E") (pinfunction "E_E") (pintype "bidirectional"))
      (node (ref "µC") (pin "38") (pinfunction "RD0/PSP0_38") (pintype "bidirectional"))
    )
    (net (code "51") (name "Net-(µCA-RD1{slash}PSP1)") (class "Default")
      (node (ref "CON1") (pin "RS") (pinfunction "RS_RS") (pintype "bidirectional"))
      (node (ref "µC") (pin "39") (pinfunction "RD1/PSP1_39") (pintype "bidirectional"))
    )
    (net (code "52") (name "Net-(µCA-RD2{slash}PSP2)") (class "Default")
      (node (ref "CON1") (pin "R/W") (pinfunction "R/W_R/W") (pintype "bidirectional"))
      (node (ref "µC") (pin "40") (pinfunction "RD2/PSP2_40") (pintype "bidirectional"))
    )
    (net (code "53") (name "Net-(µCA-RD4{slash}PSP4)") (class "Default")
      (node (ref "CON1") (pin "DB4") (pinfunction "DB4_DB4") (pintype "bidirectional"))
      (node (ref "µC") (pin "2") (pinfunction "RD4/PSP4_2") (pintype "bidirectional"))
    )
    (net (code "54") (name "Net-(µCA-RD5{slash}PSP5)") (class "Default")
      (node (ref "CON1") (pin "DB5") (pinfunction "DB5_DB5") (pintype "bidirectional"))
      (node (ref "µC") (pin "3") (pinfunction "RD5/PSP5_3") (pintype "bidirectional"))
    )
    (net (code "55") (name "Net-(µCA-RD6{slash}PSP6)") (class "Default")
      (node (ref "CON1") (pin "DB6") (pinfunction "DB6_DB6") (pintype "bidirectional"))
      (node (ref "µC") (pin "4") (pinfunction "RD6/PSP6_4") (pintype "bidirectional"))
    )
    (net (code "56") (name "Net-(µCA-RD7{slash}PSP7)") (class "Default")
      (node (ref "CON1") (pin "DB7") (pinfunction "DB7_DB7") (pintype "bidirectional"))
      (node (ref "µC") (pin "5") (pinfunction "RD7/PSP7_5") (pintype "bidirectional"))
    )
    (net (code "57") (name "unconnected-(SL2-Pad6)") (class "Default")
      (node (ref "SL2") (pin "6") (pinfunction "6_6") (pintype "passive"))
    )
    (net (code "58") (name "unconnected-(X1-Pad2)") (class "Default")
      (node (ref "X1") (pin "2") (pinfunction "2_2") (pintype "passive"))
    )
    (net (code "59") (name "unconnected-(X1-Pad3)") (class "Default")
      (node (ref "X1") (pin "3") (pinfunction "3_3") (pintype "passive"))
    )
    (net (code "60") (name "unconnected-(X1-Pad4)") (class "Default")
      (node (ref "X1") (pin "4") (pinfunction "4_4") (pintype "passive"))
    )
    (net (code "61") (name "unconnected-(µCA-RA4{slash}T0CLK-Pad23)") (class "Default")
      (node (ref "µC") (pin "23") (pinfunction "RA4/T0CLK_23") (pintype "bidirectional"))
    )
    (net (code "62") (name "unconnected-(µCA-RB5{slash}PGM{slash}(ICSP_VLVP)-Pad15)") (class "Default")
      (node (ref "µC") (pin "15") (pinfunction "RB5/PGM/(ICSP_VLVP)_15") (pintype "bidirectional"))
    )
    (net (code "63") (name "unconnected-(µCA-RC2{slash}CCP1-Pad36)") (class "Default")
      (node (ref "µC") (pin "36") (pinfunction "RC2/CCP1_36") (pintype "bidirectional"))
    )
    (net (code "64") (name "unconnected-(µCA-RC3{slash}SCK{slash}SCL-Pad37)") (class "Default")
      (node (ref "µC") (pin "37") (pinfunction "RC3/SCK/SCL_37") (pintype "bidirectional"))
    )
    (net (code "65") (name "unconnected-(µCA-RC4{slash}SDI{slash}SDA-Pad42)") (class "Default")
      (node (ref "µC") (pin "42") (pinfunction "RC4/SDI/SDA_42") (pintype "bidirectional"))
    )
    (net (code "66") (name "unconnected-(µCA-RC5{slash}SDO-Pad43)") (class "Default")
      (node (ref "µC") (pin "43") (pinfunction "RC5/SDO_43") (pintype "bidirectional"))
    )
    (net (code "67") (name "unconnected-(µCA-RC6{slash}TX{slash}CK-Pad44)") (class "Default")
      (node (ref "µC") (pin "44") (pinfunction "RC6/TX/CK_44") (pintype "bidirectional"))
    )
    (net (code "68") (name "unconnected-(µCA-RC7{slash}RX{slash}DT-Pad1)") (class "Default")
      (node (ref "µC") (pin "1") (pinfunction "RC7/RX/DT_1") (pintype "bidirectional"))
    )
    (net (code "69") (name "unconnected-(µCA-RD3{slash}PSP3-Pad41)") (class "Default")
      (node (ref "µC") (pin "41") (pinfunction "RD3/PSP3_41") (pintype "bidirectional"))
    )
    (net (code "70") (name "unconnected-(µCA-RE0{slash}RD{slash}AN5-Pad25)") (class "Default")
      (node (ref "µC") (pin "25") (pinfunction "RE0/RD/AN5_25") (pintype "bidirectional"))
    )
    (net (code "71") (name "unconnected-(µCA-RE1{slash}WR{slash}AN6-Pad26)") (class "Default")
      (node (ref "µC") (pin "26") (pinfunction "RE1/WR/AN6_26") (pintype "bidirectional"))
    )
    (net (code "72") (name "unconnected-(µCA-RE2{slash}CS{slash}AN7-Pad27)") (class "Default")
      (node (ref "µC") (pin "27") (pinfunction "RE2/CS/AN7_27") (pintype "bidirectional"))
    )
  )
)
